# Radial-V_Ext.net
KiCad netlist of a schematic drawn in EAGLE
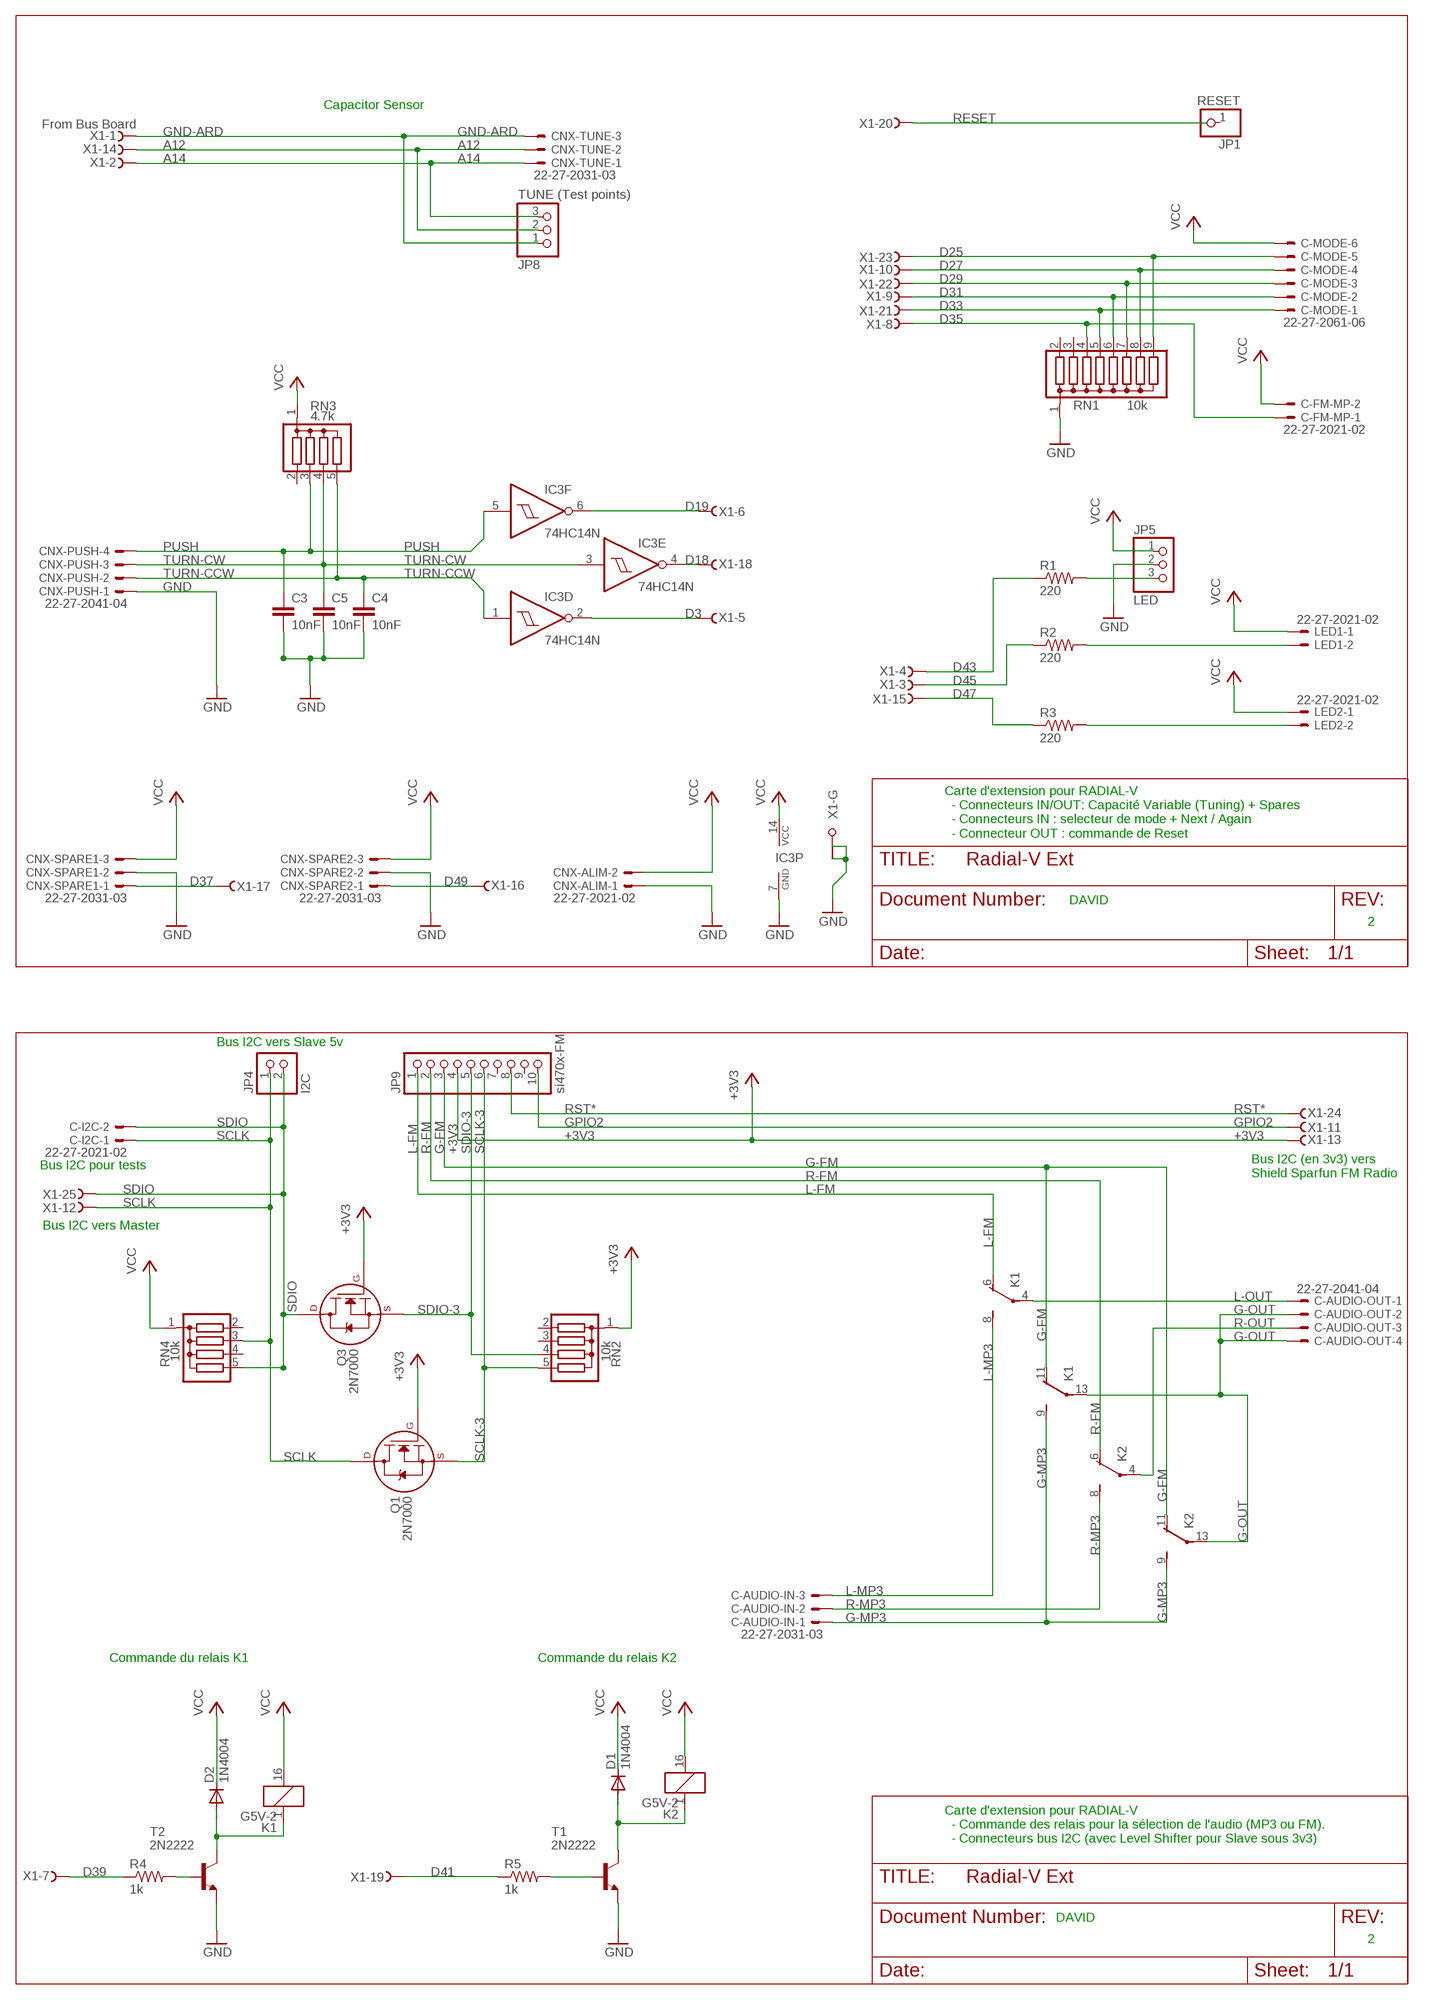
[diagram p0: schematic, sheet 1]

(export (version "E")
  (design (tool "Eeschema 10.0.6"))
  (components
    (comp (ref "C-AUDIO-IN")
      (value "22-27-2031-03")
      (footprint "eagle-import:6410-03")
      (fields (field (name "OC_FARNELL") "2366181"))
      (libsource (lib "eagle-import") (part "22-?-0327-2031"))
    )
    (comp (ref "C-AUDIO-OUT")
      (value "22-27-2041-04")
      (footprint "eagle-import:6410-04")
      (libsource (lib "eagle-import") (part "22-?-0427-2041"))
    )
    (comp (ref "C-FM-MP")
      (value "22-27-2021-02")
      (footprint "eagle-import:6410-02")
      (libsource (lib "eagle-import") (part "22-?-0227-2021"))
    )
    (comp (ref "C-I2C")
      (value "22-27-2021-02")
      (footprint "eagle-import:6410-02")
      (libsource (lib "eagle-import") (part "22-?-0227-2021"))
    )
    (comp (ref "C-MODE")
      (value "22-27-2061-06")
      (footprint "eagle-import:6410-06")
      (libsource (lib "eagle-import") (part "22-?-0627-2061"))
    )
    (comp (ref "C3")
      (value "10nF")
      (footprint "eagle-import:C050-050X075")
      (libsource (lib "eagle-import") (part "C-EU050-050X075"))
    )
    (comp (ref "C4")
      (value "10nF")
      (footprint "eagle-import:C050-050X075")
      (libsource (lib "eagle-import") (part "C-EU050-050X075"))
    )
    (comp (ref "C5")
      (value "10nF")
      (footprint "eagle-import:C050-050X075")
      (libsource (lib "eagle-import") (part "C-EU050-050X075"))
    )
    (comp (ref "CNX-ALIM")
      (value "22-27-2021-02")
      (footprint "eagle-import:6410-02")
      (libsource (lib "eagle-import") (part "22-?-0227-2021"))
    )
    (comp (ref "CNX-PUSH")
      (value "22-27-2041-04")
      (footprint "eagle-import:6410-04")
      (libsource (lib "eagle-import") (part "22-?-0427-2041"))
    )
    (comp (ref "CNX-SPARE1")
      (value "22-27-2031-03")
      (footprint "eagle-import:6410-03")
      (fields (field (name "OC_FARNELL") "2366181"))
      (libsource (lib "eagle-import") (part "22-?-0327-2031"))
    )
    (comp (ref "CNX-SPARE2")
      (value "22-27-2031-03")
      (footprint "eagle-import:6410-03")
      (fields (field (name "OC_FARNELL") "2366181"))
      (libsource (lib "eagle-import") (part "22-?-0327-2031"))
    )
    (comp (ref "CNX-TUNE")
      (value "22-27-2031-03")
      (footprint "eagle-import:6410-03")
      (libsource (lib "eagle-import") (part "22-?-0327-2031"))
    )
    (comp (ref "D1")
      (value "1N4004")
      (footprint "eagle-import:DO41-10")
      (libsource (lib "eagle-import") (part "1N4004"))
    )
    (comp (ref "D2")
      (value "1N4004")
      (footprint "eagle-import:DO41-10")
      (libsource (lib "eagle-import") (part "1N4004"))
    )
    (comp (ref "IC3")
      (value "74HC14N")
      (footprint "eagle-import:DIL14")
      (libsource (lib "eagle-import") (part "7414NHC"))
    )
    (comp (ref "JP1")
      (value "RESET")
      (footprint "eagle-import:1X01")
      (libsource (lib "eagle-import") (part "PINHD-1X1"))
    )
    (comp (ref "JP4")
      (value "I2C")
      (footprint "eagle-import:1X02")
      (libsource (lib "eagle-import") (part "PINHD-1X2"))
    )
    (comp (ref "JP5")
      (value "LED")
      (footprint "eagle-import:1X03")
      (libsource (lib "eagle-import") (part "PINHD-1X3"))
    )
    (comp (ref "JP8")
      (value "TUNE (Test points)")
      (footprint "eagle-import:1X03")
      (libsource (lib "eagle-import") (part "PINHD-1X3"))
    )
    (comp (ref "JP9")
      (value "si470x-FM")
      (footprint "eagle-import:1X10")
      (libsource (lib "eagle-import") (part "PINHD-1X10"))
    )
    (comp (ref "K1")
      (value "G5V-2")
      (footprint "eagle-import:G5V-2")
      (fields (field (name "MPN") "G5V-2 5DC"))
      (libsource (lib "eagle-import") (part "G5V-2"))
    )
    (comp (ref "K2")
      (value "G5V-2")
      (footprint "eagle-import:G5V-2")
      (fields (field (name "MPN") "G5V-2 5DC"))
      (libsource (lib "eagle-import") (part "G5V-2"))
    )
    (comp (ref "LED1")
      (value "22-27-2021-02")
      (footprint "eagle-import:6410-02")
      (libsource (lib "eagle-import") (part "22-?-0227-2021"))
    )
    (comp (ref "LED2")
      (value "22-27-2021-02")
      (footprint "eagle-import:6410-02")
      (libsource (lib "eagle-import") (part "22-?-0227-2021"))
    )
    (comp (ref "Q1")
      (value "2N7000")
      (footprint "eagle-import:TO-92")
      (libsource (lib "eagle-import") (part "2N700_TO920"))
    )
    (comp (ref "Q3")
      (value "2N7000")
      (footprint "eagle-import:TO-92")
      (libsource (lib "eagle-import") (part "2N700_TO920"))
    )
    (comp (ref "R1")
      (value "220")
      (footprint "eagle-import:0411_15")
      (libsource (lib "eagle-import") (part "R-US_0411/15"))
    )
    (comp (ref "R2")
      (value "220")
      (footprint "eagle-import:0411_15")
      (libsource (lib "eagle-import") (part "R-US_0411/15"))
    )
    (comp (ref "R3")
      (value "220")
      (footprint "eagle-import:0411_15")
      (libsource (lib "eagle-import") (part "R-US_0411/15"))
    )
    (comp (ref "R4")
      (value "1k")
      (footprint "eagle-import:0411_15")
      (libsource (lib "eagle-import") (part "R-US_0411/15"))
    )
    (comp (ref "R5")
      (value "1k")
      (footprint "eagle-import:0411_15")
      (libsource (lib "eagle-import") (part "R-US_0411/15"))
    )
    (comp (ref "RN1")
      (value "10k")
      (footprint "eagle-import:SIL9")
      (libsource (lib "eagle-import") (part "G08R"))
    )
    (comp (ref "RN2")
      (value "10k")
      (footprint "eagle-import:SIL5")
      (libsource (lib "eagle-import") (part "G04R"))
    )
    (comp (ref "RN3")
      (value "4.7k")
      (footprint "eagle-import:SIL5")
      (libsource (lib "eagle-import") (part "G04R"))
    )
    (comp (ref "RN4")
      (value "10k")
      (footprint "eagle-import:SIL5")
      (libsource (lib "eagle-import") (part "G04R"))
    )
    (comp (ref "T1")
      (value "2N2222")
      (footprint "eagle-import:TO18")
      (libsource (lib "eagle-import") (part "2N2222"))
    )
    (comp (ref "T2")
      (value "2N2222")
      (footprint "eagle-import:TO18")
      (libsource (lib "eagle-import") (part "2N2222"))
    )
    (comp (ref "X1")
      (value "From Bus Board")
      (footprint "eagle-import:F25HP")
      (libsource (lib "eagle-import") (part "F25HPS"))
    )
  )
  (nets
    (net (code "1") (name "+3V3") (class "Default")
      (node (ref "JP9") (pin "4") (pinfunction "4_4") (pintype "passive"))
      (node (ref "Q1") (pin "2") (pinfunction "G_2") (pintype "tri_state"))
      (node (ref "Q3") (pin "2") (pinfunction "G_2") (pintype "tri_state"))
      (node (ref "RN2") (pin "1") (pinfunction "1_1") (pintype "passive"))
      (node (ref "X1") (pin "13") (pinfunction "F_13") (pintype "passive"))
    )
    (net (code "2") (name "/A12") (class "Default")
      (node (ref "CNX-TUNE") (pin "2") (pinfunction "S_2") (pintype "passive"))
      (node (ref "JP8") (pin "2") (pinfunction "2_2") (pintype "passive"))
      (node (ref "X1") (pin "14") (pinfunction "F_14") (pintype "passive"))
    )
    (net (code "3") (name "/A14") (class "Default")
      (node (ref "CNX-TUNE") (pin "1") (pinfunction "S_1") (pintype "passive"))
      (node (ref "JP8") (pin "3") (pinfunction "3_3") (pintype "passive"))
      (node (ref "X1") (pin "2") (pinfunction "F_2") (pintype "passive"))
    )
    (net (code "4") (name "/D3") (class "Default")
      (node (ref "IC3") (pin "2") (pinfunction "O_2") (pintype "output"))
      (node (ref "X1") (pin "5") (pinfunction "F_5") (pintype "passive"))
    )
    (net (code "5") (name "/D18") (class "Default")
      (node (ref "IC3") (pin "4") (pinfunction "O_4") (pintype "output"))
      (node (ref "X1") (pin "18") (pinfunction "F_18") (pintype "passive"))
    )
    (net (code "6") (name "/D19") (class "Default")
      (node (ref "IC3") (pin "6") (pinfunction "O_6") (pintype "output"))
      (node (ref "X1") (pin "6") (pinfunction "F_6") (pintype "passive"))
    )
    (net (code "7") (name "/D25") (class "Default")
      (node (ref "C-MODE") (pin "5") (pinfunction "S_5") (pintype "passive"))
      (node (ref "RN1") (pin "9") (pinfunction "9_9") (pintype "passive"))
      (node (ref "X1") (pin "23") (pinfunction "F_23") (pintype "passive"))
    )
    (net (code "8") (name "/D27") (class "Default")
      (node (ref "C-MODE") (pin "4") (pinfunction "S_4") (pintype "passive"))
      (node (ref "RN1") (pin "8") (pinfunction "8_8") (pintype "passive"))
      (node (ref "X1") (pin "10") (pinfunction "F_10") (pintype "passive"))
    )
    (net (code "9") (name "/D29") (class "Default")
      (node (ref "C-MODE") (pin "3") (pinfunction "S_3") (pintype "passive"))
      (node (ref "RN1") (pin "7") (pinfunction "7_7") (pintype "passive"))
      (node (ref "X1") (pin "22") (pinfunction "F_22") (pintype "passive"))
    )
    (net (code "10") (name "/D31") (class "Default")
      (node (ref "C-MODE") (pin "2") (pinfunction "S_2") (pintype "passive"))
      (node (ref "RN1") (pin "6") (pinfunction "6_6") (pintype "passive"))
      (node (ref "X1") (pin "9") (pinfunction "F_9") (pintype "passive"))
    )
    (net (code "11") (name "/D33") (class "Default")
      (node (ref "C-MODE") (pin "1") (pinfunction "S_1") (pintype "passive"))
      (node (ref "RN1") (pin "5") (pinfunction "5_5") (pintype "passive"))
      (node (ref "X1") (pin "21") (pinfunction "F_21") (pintype "passive"))
    )
    (net (code "12") (name "/D35") (class "Default")
      (node (ref "C-FM-MP") (pin "1") (pinfunction "S_1") (pintype "passive"))
      (node (ref "RN1") (pin "4") (pinfunction "4_4") (pintype "passive"))
      (node (ref "X1") (pin "8") (pinfunction "F_8") (pintype "passive"))
    )
    (net (code "13") (name "/D37") (class "Default")
      (node (ref "CNX-SPARE1") (pin "1") (pinfunction "S_1") (pintype "passive"))
      (node (ref "X1") (pin "17") (pinfunction "F_17") (pintype "passive"))
    )
    (net (code "14") (name "/D39") (class "Default")
      (node (ref "R4") (pin "1") (pinfunction "1_1") (pintype "passive"))
      (node (ref "X1") (pin "7") (pinfunction "F_7") (pintype "passive"))
    )
    (net (code "15") (name "/D41") (class "Default")
      (node (ref "R5") (pin "1") (pinfunction "1_1") (pintype "passive"))
      (node (ref "X1") (pin "19") (pinfunction "F_19") (pintype "passive"))
    )
    (net (code "16") (name "/D43") (class "Default")
      (node (ref "R1") (pin "1") (pinfunction "1_1") (pintype "passive"))
      (node (ref "X1") (pin "4") (pinfunction "F_4") (pintype "passive"))
    )
    (net (code "17") (name "/D45") (class "Default")
      (node (ref "R2") (pin "1") (pinfunction "1_1") (pintype "passive"))
      (node (ref "X1") (pin "3") (pinfunction "F_3") (pintype "passive"))
    )
    (net (code "18") (name "/D47") (class "Default")
      (node (ref "R3") (pin "1") (pinfunction "1_1") (pintype "passive"))
      (node (ref "X1") (pin "15") (pinfunction "F_15") (pintype "passive"))
    )
    (net (code "19") (name "/D49") (class "Default")
      (node (ref "CNX-SPARE2") (pin "1") (pinfunction "S_1") (pintype "passive"))
      (node (ref "X1") (pin "16") (pinfunction "F_16") (pintype "passive"))
    )
    (net (code "20") (name "/G-FM") (class "Default")
      (node (ref "JP9") (pin "3") (pinfunction "3_3") (pintype "passive"))
      (node (ref "K1") (pin "11") (pinfunction "O_11") (pintype "passive"))
      (node (ref "K2") (pin "11") (pinfunction "O_11") (pintype "passive"))
    )
    (net (code "21") (name "/G-MP3") (class "Default")
      (node (ref "C-AUDIO-IN") (pin "1") (pinfunction "S_1") (pintype "passive"))
      (node (ref "K1") (pin "9") (pinfunction "S_9") (pintype "passive"))
      (node (ref "K2") (pin "9") (pinfunction "S_9") (pintype "passive"))
    )
    (net (code "22") (name "/G-OUT") (class "Default")
      (node (ref "C-AUDIO-OUT") (pin "2") (pinfunction "S_2") (pintype "passive"))
      (node (ref "C-AUDIO-OUT") (pin "4") (pinfunction "S_4") (pintype "passive"))
      (node (ref "K1") (pin "13") (pinfunction "P_13") (pintype "passive"))
      (node (ref "K2") (pin "13") (pinfunction "P_13") (pintype "passive"))
    )
    (net (code "23") (name "/GND-ARD") (class "Default")
      (node (ref "CNX-TUNE") (pin "3") (pinfunction "S_3") (pintype "passive"))
      (node (ref "JP8") (pin "1") (pinfunction "1_1") (pintype "passive"))
      (node (ref "X1") (pin "1") (pinfunction "F_1") (pintype "passive"))
    )
    (net (code "24") (name "/GPIO2") (class "Default")
      (node (ref "JP9") (pin "10") (pinfunction "10_10") (pintype "passive"))
      (node (ref "X1") (pin "11") (pinfunction "F_11") (pintype "passive"))
    )
    (net (code "25") (name "/L-FM") (class "Default")
      (node (ref "JP9") (pin "1") (pinfunction "1_1") (pintype "passive"))
      (node (ref "K1") (pin "6") (pinfunction "O_6") (pintype "passive"))
    )
    (net (code "26") (name "/L-MP3") (class "Default")
      (node (ref "C-AUDIO-IN") (pin "3") (pinfunction "S_3") (pintype "passive"))
      (node (ref "K1") (pin "8") (pinfunction "S_8") (pintype "passive"))
    )
    (net (code "27") (name "/L-OUT") (class "Default")
      (node (ref "C-AUDIO-OUT") (pin "1") (pinfunction "S_1") (pintype "passive"))
      (node (ref "K1") (pin "4") (pinfunction "P_4") (pintype "passive"))
    )
    (net (code "28") (name "/PUSH") (class "Default")
      (node (ref "C3") (pin "1") (pinfunction "1_1") (pintype "passive"))
      (node (ref "CNX-PUSH") (pin "4") (pinfunction "S_4") (pintype "passive"))
      (node (ref "IC3") (pin "5") (pinfunction "I_5") (pintype "input"))
      (node (ref "RN3") (pin "3") (pinfunction "3_3") (pintype "passive"))
    )
    (net (code "29") (name "/R-FM") (class "Default")
      (node (ref "JP9") (pin "2") (pinfunction "2_2") (pintype "passive"))
      (node (ref "K2") (pin "6") (pinfunction "O_6") (pintype "passive"))
    )
    (net (code "30") (name "/R-MP3") (class "Default")
      (node (ref "C-AUDIO-IN") (pin "2") (pinfunction "S_2") (pintype "passive"))
      (node (ref "K2") (pin "8") (pinfunction "S_8") (pintype "passive"))
    )
    (net (code "31") (name "/R-OUT") (class "Default")
      (node (ref "C-AUDIO-OUT") (pin "3") (pinfunction "S_3") (pintype "passive"))
      (node (ref "K2") (pin "4") (pinfunction "P_4") (pintype "passive"))
    )
    (net (code "32") (name "/RESET") (class "Default")
      (node (ref "X1") (pin "20") (pinfunction "F_20") (pintype "passive"))
    )
    (net (code "33") (name "/RST*") (class "Default")
      (node (ref "JP9") (pin "8") (pinfunction "8_8") (pintype "passive"))
      (node (ref "X1") (pin "24") (pinfunction "F_24") (pintype "passive"))
    )
    (net (code "34") (name "/SCLK") (class "Default")
      (node (ref "C-I2C") (pin "1") (pinfunction "S_1") (pintype "passive"))
      (node (ref "JP4") (pin "1") (pinfunction "1_1") (pintype "passive"))
      (node (ref "Q1") (pin "3") (pinfunction "D_3") (pintype "bidirectional"))
      (node (ref "RN4") (pin "3") (pinfunction "3_3") (pintype "passive"))
      (node (ref "X1") (pin "12") (pinfunction "F_12") (pintype "passive"))
    )
    (net (code "35") (name "/SCLK-3") (class "Default")
      (node (ref "JP9") (pin "6") (pinfunction "6_6") (pintype "passive"))
      (node (ref "Q1") (pin "1") (pinfunction "S_1") (pintype "bidirectional"))
      (node (ref "RN2") (pin "5") (pinfunction "5_5") (pintype "passive"))
    )
    (net (code "36") (name "/SDIO") (class "Default")
      (node (ref "C-I2C") (pin "2") (pinfunction "S_2") (pintype "passive"))
      (node (ref "JP4") (pin "2") (pinfunction "2_2") (pintype "passive"))
      (node (ref "Q3") (pin "3") (pinfunction "D_3") (pintype "bidirectional"))
      (node (ref "RN4") (pin "5") (pinfunction "5_5") (pintype "passive"))
      (node (ref "X1") (pin "25") (pinfunction "F_25") (pintype "passive"))
    )
    (net (code "37") (name "/SDIO-3") (class "Default")
      (node (ref "JP9") (pin "5") (pinfunction "5_5") (pintype "passive"))
      (node (ref "Q3") (pin "1") (pinfunction "S_1") (pintype "bidirectional"))
      (node (ref "RN2") (pin "4") (pinfunction "4_4") (pintype "passive"))
    )
    (net (code "38") (name "/TURN-CCW") (class "Default")
      (node (ref "C4") (pin "1") (pinfunction "1_1") (pintype "passive"))
      (node (ref "CNX-PUSH") (pin "2") (pinfunction "S_2") (pintype "passive"))
      (node (ref "IC3") (pin "1") (pinfunction "I_1") (pintype "input"))
      (node (ref "RN3") (pin "5") (pinfunction "5_5") (pintype "passive"))
    )
    (net (code "39") (name "/TURN-CW") (class "Default")
      (node (ref "C5") (pin "1") (pinfunction "1_1") (pintype "passive"))
      (node (ref "CNX-PUSH") (pin "3") (pinfunction "S_3") (pintype "passive"))
      (node (ref "IC3") (pin "3") (pinfunction "I_3") (pintype "input"))
      (node (ref "RN3") (pin "4") (pinfunction "4_4") (pintype "passive"))
    )
    (net (code "40") (name "GND") (class "Default")
      (node (ref "C3") (pin "2") (pinfunction "2_2") (pintype "passive"))
      (node (ref "C4") (pin "2") (pinfunction "2_2") (pintype "passive"))
      (node (ref "C5") (pin "2") (pinfunction "2_2") (pintype "passive"))
      (node (ref "CNX-ALIM") (pin "1") (pinfunction "S_1") (pintype "passive"))
      (node (ref "CNX-PUSH") (pin "1") (pinfunction "S_1") (pintype "passive"))
      (node (ref "CNX-SPARE1") (pin "2") (pinfunction "S_2") (pintype "passive"))
      (node (ref "CNX-SPARE2") (pin "2") (pinfunction "S_2") (pintype "passive"))
      (node (ref "IC3") (pin "7") (pinfunction "GND_7") (pintype "power_in"))
      (node (ref "JP5") (pin "2") (pinfunction "2_2") (pintype "passive"))
      (node (ref "RN1") (pin "1") (pinfunction "1_1") (pintype "passive"))
      (node (ref "T1") (pin "1") (pinfunction "E_1") (pintype "passive"))
      (node (ref "T2") (pin "1") (pinfunction "E_1") (pintype "passive"))
      (node (ref "X1") (pin "G1") (pinfunction "G1_G1") (pintype "passive"))
      (node (ref "X1") (pin "G2") (pinfunction "G2_G2") (pintype "passive"))
    )
    (net (code "41") (name "Net-(JP5-Pad3)") (class "Default")
      (node (ref "JP5") (pin "3") (pinfunction "3_3") (pintype "passive"))
      (node (ref "R1") (pin "2") (pinfunction "2_2") (pintype "passive"))
    )
    (net (code "42") (name "Net-(LED1B-S)") (class "Default")
      (node (ref "LED1") (pin "2") (pinfunction "S_2") (pintype "passive"))
      (node (ref "R2") (pin "2") (pinfunction "2_2") (pintype "passive"))
    )
    (net (code "43") (name "Net-(LED2B-S)") (class "Default")
      (node (ref "LED2") (pin "2") (pinfunction "S_2") (pintype "passive"))
      (node (ref "R3") (pin "2") (pinfunction "2_2") (pintype "passive"))
    )
    (net (code "44") (name "Net-(T1-B)") (class "Default")
      (node (ref "R5") (pin "2") (pinfunction "2_2") (pintype "passive"))
      (node (ref "T1") (pin "2") (pinfunction "B_2") (pintype "passive"))
    )
    (net (code "45") (name "Net-(T1-C)") (class "Default")
      (node (ref "D1") (pin "A") (pinfunction "A_A") (pintype "passive"))
      (node (ref "K2") (pin "1") (pinfunction "1_1") (pintype "passive"))
      (node (ref "T1") (pin "3") (pinfunction "C_3") (pintype "passive"))
    )
    (net (code "46") (name "Net-(T2-B)") (class "Default")
      (node (ref "R4") (pin "2") (pinfunction "2_2") (pintype "passive"))
      (node (ref "T2") (pin "2") (pinfunction "B_2") (pintype "passive"))
    )
    (net (code "47") (name "Net-(T2-C)") (class "Default")
      (node (ref "D2") (pin "A") (pinfunction "A_A") (pintype "passive"))
      (node (ref "K1") (pin "1") (pinfunction "1_1") (pintype "passive"))
      (node (ref "T2") (pin "3") (pinfunction "C_3") (pintype "passive"))
    )
    (net (code "48") (name "VCC") (class "Default")
      (node (ref "C-FM-MP") (pin "2") (pinfunction "S_2") (pintype "passive"))
      (node (ref "C-MODE") (pin "6") (pinfunction "S_6") (pintype "passive"))
      (node (ref "CNX-ALIM") (pin "2") (pinfunction "S_2") (pintype "passive"))
      (node (ref "CNX-SPARE1") (pin "3") (pinfunction "S_3") (pintype "passive"))
      (node (ref "CNX-SPARE2") (pin "3") (pinfunction "S_3") (pintype "passive"))
      (node (ref "D1") (pin "C") (pinfunction "C_C") (pintype "passive"))
      (node (ref "D2") (pin "C") (pinfunction "C_C") (pintype "passive"))
      (node (ref "IC3") (pin "14") (pinfunction "VCC_14") (pintype "power_in"))
      (node (ref "JP5") (pin "1") (pinfunction "1_1") (pintype "passive"))
      (node (ref "K1") (pin "16") (pinfunction "2_16") (pintype "passive"))
      (node (ref "K2") (pin "16") (pinfunction "2_16") (pintype "passive"))
      (node (ref "LED1") (pin "1") (pinfunction "S_1") (pintype "passive"))
      (node (ref "LED2") (pin "1") (pinfunction "S_1") (pintype "passive"))
      (node (ref "RN3") (pin "1") (pinfunction "1_1") (pintype "passive"))
      (node (ref "RN4") (pin "1") (pinfunction "1_1") (pintype "passive"))
    )
    (net (code "49") (name "unconnected-(JP1-Pad1)") (class "Default")
      (node (ref "JP1") (pin "1") (pinfunction "1_1") (pintype "passive"))
    )
    (net (code "50") (name "unconnected-(JP9-Pad7)") (class "Default")
      (node (ref "JP9") (pin "7") (pinfunction "7_7") (pintype "passive"))
    )
    (net (code "51") (name "unconnected-(JP9-Pad9)") (class "Default")
      (node (ref "JP9") (pin "9") (pinfunction "9_9") (pintype "passive"))
    )
    (net (code "52") (name "unconnected-(RN1-Pad2)") (class "Default")
      (node (ref "RN1") (pin "2") (pinfunction "2_2") (pintype "passive"))
    )
    (net (code "53") (name "unconnected-(RN1-Pad3)") (class "Default")
      (node (ref "RN1") (pin "3") (pinfunction "3_3") (pintype "passive"))
    )
    (net (code "54") (name "unconnected-(RN2-Pad2)") (class "Default")
      (node (ref "RN2") (pin "2") (pinfunction "2_2") (pintype "passive"))
    )
    (net (code "55") (name "unconnected-(RN2-Pad3)") (class "Default")
      (node (ref "RN2") (pin "3") (pinfunction "3_3") (pintype "passive"))
    )
    (net (code "56") (name "unconnected-(RN3-Pad2)") (class "Default")
      (node (ref "RN3") (pin "2") (pinfunction "2_2") (pintype "passive"))
    )
    (net (code "57") (name "unconnected-(RN4-Pad2)") (class "Default")
      (node (ref "RN4") (pin "2") (pinfunction "2_2") (pintype "passive"))
    )
    (net (code "58") (name "unconnected-(RN4-Pad4)") (class "Default")
      (node (ref "RN4") (pin "4") (pinfunction "4_4") (pintype "passive"))
    )
  )
)
